# CSA.net
KiCad netlist of a schematic drawn in Altium Designer
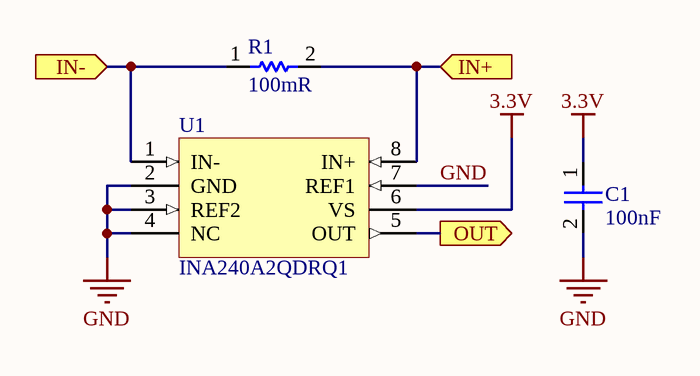
[diagram p0: CSA.SchDoc]

(export (version "E")
  (design (tool "Eeschema 10.0.6"))
  (components
    (comp (ref "C1")
      (value "100nF")
      (footprint "MURA-0603_H_0.9_N")
      (description "X7R,.1UF,20%,16V,UNMARKED, 1.0A 40V ROHS 3K<AZ")
      (fields
        (field (name "MANUFACTURER") "KEMET")
        (field (name "MANUFACTURER PART NUMBER") "C0603C104M4RAC7411")
      )
      (libsource (lib "CSA") (part "C0603C104M4RAC7411"))
    )
    (comp (ref "R1")
      (value "100mR")
      (footprint "RESC2512(6432)_N")
      (fields
        (field (name "MANUFACTURER") "Bourns")
        (field (name "MANUFACTURER PART NUMBER") "CRA2512FZR100ELF")
        (field (name "TOLERANCE") "1%")
      )
      (libsource (lib "CSA") (part "CRA2512FZR100ELF"))
    )
    (comp (ref "U1")
      (value "INA240A2QDRQ1")
      (footprint "D0008A_M")
      (description "Op Amp Single Zero Drift Amplifier 5.5V Automotive 8-Pin SOIC T/R")
      (fields (field (name "MANUFACTURER") "Texas Instruments"))
      (libsource (lib "CSA") (part "INA240A2QDRQ1"))
    )
  )
  (nets
    (net (code "1") (name "/IN+") (class "Default")
      (node (ref "R1") (pin "2") (pinfunction "2_2") (pintype "passive"))
      (node (ref "U1") (pin "8") (pinfunction "IN+_8") (pintype "input"))
    )
    (net (code "2") (name "/IN-") (class "Default")
      (node (ref "R1") (pin "1") (pinfunction "1_1") (pintype "passive"))
      (node (ref "U1") (pin "1") (pinfunction "IN-_1") (pintype "input"))
    )
    (net (code "3") (name "/OUT") (class "Default")
      (node (ref "U1") (pin "5") (pinfunction "OUT_5") (pintype "output"))
    )
    (net (code "4") (name "3.3V") (class "Default")
      (node (ref "C1") (pin "1") (pinfunction "1_1") (pintype "passive"))
      (node (ref "U1") (pin "6") (pinfunction "VS_6") (pintype "power_in"))
    )
    (net (code "5") (name "GND") (class "Default")
      (node (ref "C1") (pin "2") (pinfunction "2_2") (pintype "passive"))
      (node (ref "U1") (pin "2") (pinfunction "GND_2") (pintype "power_in"))
      (node (ref "U1") (pin "3") (pinfunction "REF2_3") (pintype "input"))
      (node (ref "U1") (pin "4") (pinfunction "NC_4") (pintype "passive"))
      (node (ref "U1") (pin "7") (pinfunction "REF1_7") (pintype "input"))
    )
  )
)
